# base_robot.net
KiCad netlist of a schematic drawn in EAGLE
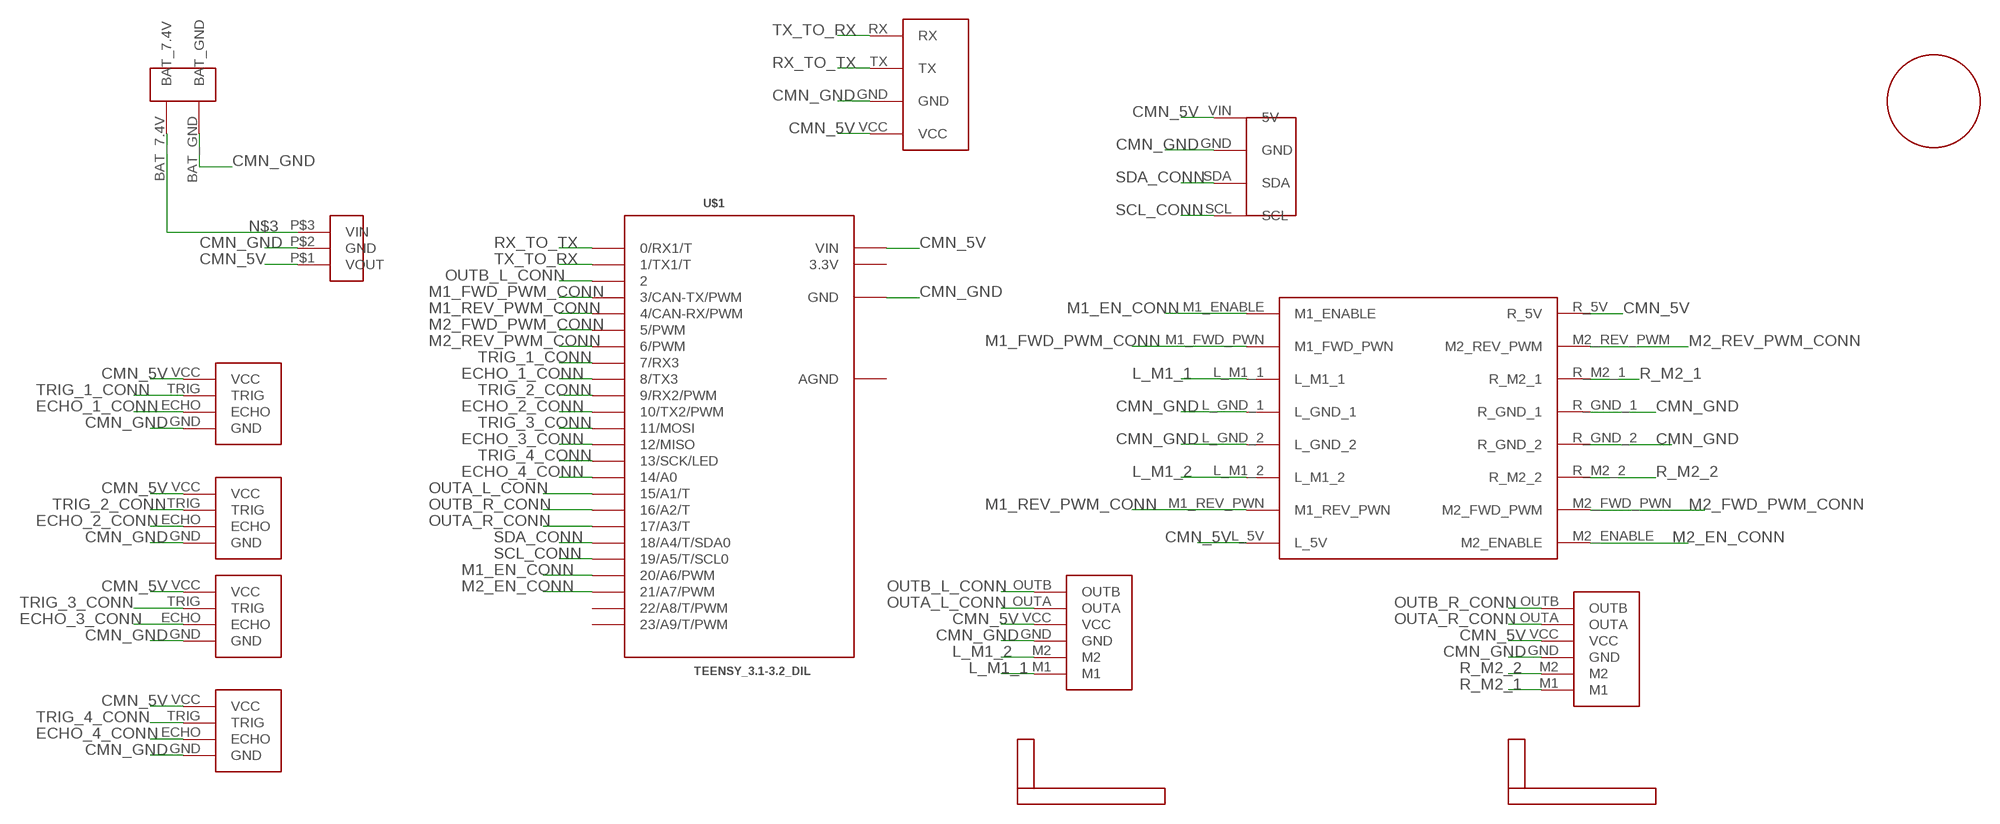
[diagram p0: schematic, sheet 1]

(export (version "E")
  (design (tool "Eeschema 10.0.6"))
  (components
    (comp (ref "U$1")
      (value "TEENSY_3.1-3.2_DIL")
      (footprint "eagle-import:TEENSY_3.0-3.2&LC_DIL")
      (libsource (lib "eagle-import") (part "TEENSY_3.1-3.2_DIL"))
    )
    (comp (ref "U$2")
      (value "MOTOR_DRIVER")
      (footprint "eagle-import:MOTOR_DRIVER")
      (libsource (lib "eagle-import") (part "MOTOR_DRIVER"))
    )
    (comp (ref "U$3")
      (value "VOLTAGE_REGULATOR")
      (footprint "eagle-import:VOLTAGE_REGULATOR")
      (libsource (lib "eagle-import") (part "VOLTAGE_REGULATOR"))
    )
    (comp (ref "U$4")
      (value "SONAR_SENSOR")
      (footprint "eagle-import:SONAR_SENSOR")
      (libsource (lib "eagle-import") (part "SONAR_SENSOR"))
    )
    (comp (ref "U$5")
      (value "SONAR_SENSOR")
      (footprint "eagle-import:SONAR_SENSOR")
      (libsource (lib "eagle-import") (part "SONAR_SENSOR"))
    )
    (comp (ref "U$6")
      (value "SONAR_SENSOR")
      (footprint "eagle-import:SONAR_SENSOR")
      (libsource (lib "eagle-import") (part "SONAR_SENSOR"))
    )
    (comp (ref "U$7")
      (value "SONAR_SENSOR")
      (footprint "eagle-import:SONAR_SENSOR")
      (libsource (lib "eagle-import") (part "SONAR_SENSOR"))
    )
    (comp (ref "U$8")
      (value "BATTERY_INPUT")
      (footprint "eagle-import:BATTERY_INPUT")
      (libsource (lib "eagle-import") (part "BATTERY_INPUT"))
    )
    (comp (ref "U$9")
      (value "MOTOR_ENCODER_25D")
      (footprint "eagle-import:MOTOR_ENCODER_25D")
      (libsource (lib "eagle-import") (part "MOTOR_ENCODER_25D"))
    )
    (comp (ref "U$10")
      (value "MOTOR_ENCODER_25D")
      (footprint "eagle-import:MOTOR_ENCODER_25D")
      (libsource (lib "eagle-import") (part "MOTOR_ENCODER_25D"))
    )
    (comp (ref "U$11")
      (value "IMU")
      (footprint "eagle-import:IMU")
      (libsource (lib "eagle-import") (part "IMU"))
    )
    (comp (ref "U$12")
      (value "HC05_BLUETOOTH")
      (footprint "eagle-import:HC05_BLUETOOTH")
      (libsource (lib "eagle-import") (part "HC05_BLUETOOTH"))
    )
    (comp (ref "U$13")
      (value "3_4_BALLCASTER")
      (footprint "eagle-import:3_4_BALLCASTER")
      (libsource (lib "eagle-import") (part "3_4_BALLCASTER"))
    )
    (comp (ref "U$14")
      (value "MOTOR_BRACKET_25D")
      (footprint "eagle-import:MOTOR_BRACKET_25D")
      (libsource (lib "eagle-import") (part "MOTOR_BRACKET_25D"))
    )
    (comp (ref "U$15")
      (value "MOTOR_BRACKET_25D")
      (footprint "eagle-import:MOTOR_BRACKET_25D")
      (libsource (lib "eagle-import") (part "MOTOR_BRACKET_25D"))
    )
  )
  (nets
    (net (code "1") (name "/3.3V") (class "Default")
      (node (ref "U$1") (pin "3.3V") (pinfunction "3.3V_3.3V") (pintype "power_in"))
    )
    (net (code "2") (name "/AGND") (class "Default")
      (node (ref "U$1") (pin "AGND") (pinfunction "AGND_AGND") (pintype "power_in"))
    )
    (net (code "3") (name "/CMN_5V") (class "Default")
      (node (ref "U$1") (pin "VIN") (pinfunction "VIN_VIN") (pintype "power_in"))
      (node (ref "U$10") (pin "VCC") (pinfunction "VCC_VCC") (pintype "bidirectional"))
      (node (ref "U$11") (pin "VIN") (pinfunction "5V_VIN") (pintype "bidirectional"))
      (node (ref "U$12") (pin "VCC") (pinfunction "VCC_VCC") (pintype "bidirectional"))
      (node (ref "U$2") (pin "L_5V") (pinfunction "L_5V_L_5V") (pintype "bidirectional"))
      (node (ref "U$2") (pin "R_5V") (pinfunction "R_5V_R_5V") (pintype "bidirectional"))
      (node (ref "U$3") (pin "P$1") (pinfunction "VOUT_P$1") (pintype "bidirectional"))
      (node (ref "U$4") (pin "VCC") (pinfunction "VCC_VCC") (pintype "bidirectional"))
      (node (ref "U$5") (pin "VCC") (pinfunction "VCC_VCC") (pintype "bidirectional"))
      (node (ref "U$6") (pin "VCC") (pinfunction "VCC_VCC") (pintype "bidirectional"))
      (node (ref "U$7") (pin "VCC") (pinfunction "VCC_VCC") (pintype "bidirectional"))
      (node (ref "U$9") (pin "VCC") (pinfunction "VCC_VCC") (pintype "bidirectional"))
    )
    (net (code "4") (name "/CMN_GND") (class "Default")
      (node (ref "U$1") (pin "GND") (pinfunction "GND_GND") (pintype "power_in"))
      (node (ref "U$10") (pin "GND") (pinfunction "GND_GND") (pintype "bidirectional"))
      (node (ref "U$11") (pin "GND") (pinfunction "GND_GND") (pintype "bidirectional"))
      (node (ref "U$12") (pin "GND") (pinfunction "GND_GND") (pintype "bidirectional"))
      (node (ref "U$2") (pin "L_GND_1") (pinfunction "L_GND_1_L_GND_1") (pintype "bidirectional"))
      (node (ref "U$2") (pin "L_GND_2") (pinfunction "L_GND_2_L_GND_2") (pintype "bidirectional"))
      (node (ref "U$2") (pin "R_GND_1") (pinfunction "R_GND_1_R_GND_1") (pintype "bidirectional"))
      (node (ref "U$2") (pin "R_GND_2") (pinfunction "R_GND_2_R_GND_2") (pintype "bidirectional"))
      (node (ref "U$3") (pin "P$2") (pinfunction "GND_P$2") (pintype "bidirectional"))
      (node (ref "U$4") (pin "GND") (pinfunction "GND_GND") (pintype "bidirectional"))
      (node (ref "U$5") (pin "GND") (pinfunction "GND_GND") (pintype "bidirectional"))
      (node (ref "U$6") (pin "GND") (pinfunction "GND_GND") (pintype "bidirectional"))
      (node (ref "U$7") (pin "GND") (pinfunction "GND_GND") (pintype "bidirectional"))
      (node (ref "U$8") (pin "BAT_GND") (pinfunction "BAT_GND_BAT_GND") (pintype "bidirectional"))
      (node (ref "U$9") (pin "GND") (pinfunction "GND_GND") (pintype "bidirectional"))
    )
    (net (code "5") (name "/ECHO_1_CONN") (class "Default")
      (node (ref "U$1") (pin "8") (pinfunction "8/TX3_8") (pintype "bidirectional"))
      (node (ref "U$4") (pin "ECHO") (pinfunction "ECHO_ECHO") (pintype "bidirectional"))
    )
    (net (code "6") (name "/ECHO_2_CONN") (class "Default")
      (node (ref "U$1") (pin "10") (pinfunction "10/TX2/PWM_10") (pintype "bidirectional"))
      (node (ref "U$5") (pin "ECHO") (pinfunction "ECHO_ECHO") (pintype "bidirectional"))
    )
    (net (code "7") (name "/ECHO_3_CONN") (class "Default")
      (node (ref "U$1") (pin "12") (pinfunction "12/MISO_12") (pintype "bidirectional"))
      (node (ref "U$6") (pin "ECHO") (pinfunction "ECHO_ECHO") (pintype "bidirectional"))
    )
    (net (code "8") (name "/ECHO_4_CONN") (class "Default")
      (node (ref "U$1") (pin "14/A0") (pinfunction "14/A0_14/A0") (pintype "bidirectional"))
      (node (ref "U$7") (pin "ECHO") (pinfunction "ECHO_ECHO") (pintype "bidirectional"))
    )
    (net (code "9") (name "/L_M1_1") (class "Default")
      (node (ref "U$2") (pin "L_M1_1") (pinfunction "L_M1_1_L_M1_1") (pintype "bidirectional"))
      (node (ref "U$9") (pin "M1") (pinfunction "M1_M1") (pintype "bidirectional"))
    )
    (net (code "10") (name "/L_M1_2") (class "Default")
      (node (ref "U$2") (pin "L_M1_2") (pinfunction "L_M1_2_L_M1_2") (pintype "bidirectional"))
      (node (ref "U$9") (pin "M2") (pinfunction "M2_M2") (pintype "bidirectional"))
    )
    (net (code "11") (name "/M1_EN_CONN") (class "Default")
      (node (ref "U$1") (pin "20/A6") (pinfunction "20/A6/PWM_20/A6") (pintype "bidirectional"))
      (node (ref "U$2") (pin "M1_ENABLE") (pinfunction "M1_ENABLE_M1_ENABLE") (pintype "bidirectional"))
    )
    (net (code "12") (name "/M1_FWD_PWM_CONN") (class "Default")
      (node (ref "U$1") (pin "3") (pinfunction "3/CAN-TX/PWM_3") (pintype "bidirectional"))
      (node (ref "U$2") (pin "M1_FWD_PWN") (pinfunction "M1_FWD_PWN_M1_FWD_PWN") (pintype "bidirectional"))
    )
    (net (code "13") (name "/M1_REV_PWM_CONN") (class "Default")
      (node (ref "U$1") (pin "4") (pinfunction "4/CAN-RX/PWM_4") (pintype "bidirectional"))
      (node (ref "U$2") (pin "M1_REV_PWN") (pinfunction "M1_REV_PWN_M1_REV_PWN") (pintype "bidirectional"))
    )
    (net (code "14") (name "/M2_EN_CONN") (class "Default")
      (node (ref "U$1") (pin "21/A7") (pinfunction "21/A7/PWM_21/A7") (pintype "bidirectional"))
      (node (ref "U$2") (pin "M2_ENABLE") (pinfunction "M2_ENABLE_M2_ENABLE") (pintype "bidirectional"))
    )
    (net (code "15") (name "/M2_FWD_PWM_CONN") (class "Default")
      (node (ref "U$1") (pin "5") (pinfunction "5/PWM_5") (pintype "bidirectional"))
      (node (ref "U$2") (pin "M2_FWD_PWN") (pinfunction "M2_FWD_PWM_M2_FWD_PWN") (pintype "bidirectional"))
    )
    (net (code "16") (name "/M2_REV_PWM_CONN") (class "Default")
      (node (ref "U$1") (pin "6") (pinfunction "6/PWM_6") (pintype "bidirectional"))
      (node (ref "U$2") (pin "M2_REV_PWM") (pinfunction "M2_REV_PWM_M2_REV_PWM") (pintype "bidirectional"))
    )
    (net (code "17") (name "/N$3") (class "Default")
      (node (ref "U$3") (pin "P$3") (pinfunction "VIN_P$3") (pintype "bidirectional"))
      (node (ref "U$8") (pin "BAT_7.4V") (pinfunction "BAT_7.4V_BAT_7.4V") (pintype "bidirectional"))
    )
    (net (code "18") (name "/OUTA_L_CONN") (class "Default")
      (node (ref "U$1") (pin "15/A1") (pinfunction "15/A1/T_15/A1") (pintype "bidirectional"))
      (node (ref "U$9") (pin "OUTA") (pinfunction "OUTA_OUTA") (pintype "bidirectional"))
    )
    (net (code "19") (name "/OUTA_R_CONN") (class "Default")
      (node (ref "U$1") (pin "17/A3") (pinfunction "17/A3/T_17/A3") (pintype "bidirectional"))
      (node (ref "U$10") (pin "OUTA") (pinfunction "OUTA_OUTA") (pintype "bidirectional"))
    )
    (net (code "20") (name "/OUTB_L_CONN") (class "Default")
      (node (ref "U$1") (pin "2") (pinfunction "2_2") (pintype "bidirectional"))
      (node (ref "U$9") (pin "OUTB") (pinfunction "OUTB_OUTB") (pintype "bidirectional"))
    )
    (net (code "21") (name "/OUTB_R_CONN") (class "Default")
      (node (ref "U$1") (pin "16/A2") (pinfunction "16/A2/T_16/A2") (pintype "bidirectional"))
      (node (ref "U$10") (pin "OUTB") (pinfunction "OUTB_OUTB") (pintype "bidirectional"))
    )
    (net (code "22") (name "/RX_TO_TX") (class "Default")
      (node (ref "U$1") (pin "0") (pinfunction "0/RX1/T_0") (pintype "bidirectional"))
      (node (ref "U$12") (pin "TX") (pinfunction "TX_TX") (pintype "bidirectional"))
    )
    (net (code "23") (name "/R_M2_1") (class "Default")
      (node (ref "U$10") (pin "M1") (pinfunction "M1_M1") (pintype "bidirectional"))
      (node (ref "U$2") (pin "R_M2_1") (pinfunction "R_M2_1_R_M2_1") (pintype "bidirectional"))
    )
    (net (code "24") (name "/R_M2_2") (class "Default")
      (node (ref "U$10") (pin "M2") (pinfunction "M2_M2") (pintype "bidirectional"))
      (node (ref "U$2") (pin "R_M2_2") (pinfunction "R_M2_2_R_M2_2") (pintype "bidirectional"))
    )
    (net (code "25") (name "/SCL_CONN") (class "Default")
      (node (ref "U$1") (pin "19/A5") (pinfunction "19/A5/T/SCL0_19/A5") (pintype "bidirectional"))
      (node (ref "U$11") (pin "SCL") (pinfunction "SCL_SCL") (pintype "bidirectional"))
    )
    (net (code "26") (name "/SDA_CONN") (class "Default")
      (node (ref "U$1") (pin "18/A4") (pinfunction "18/A4/T/SDA0_18/A4") (pintype "bidirectional"))
      (node (ref "U$11") (pin "SDA") (pinfunction "SDA_SDA") (pintype "bidirectional"))
    )
    (net (code "27") (name "/TRIG_1_CONN") (class "Default")
      (node (ref "U$1") (pin "7") (pinfunction "7/RX3_7") (pintype "bidirectional"))
      (node (ref "U$4") (pin "TRIG") (pinfunction "TRIG_TRIG") (pintype "bidirectional"))
    )
    (net (code "28") (name "/TRIG_2_CONN") (class "Default")
      (node (ref "U$1") (pin "9") (pinfunction "9/RX2/PWM_9") (pintype "bidirectional"))
      (node (ref "U$5") (pin "TRIG") (pinfunction "TRIG_TRIG") (pintype "bidirectional"))
    )
    (net (code "29") (name "/TRIG_3_CONN") (class "Default")
      (node (ref "U$1") (pin "11") (pinfunction "11/MOSI_11") (pintype "bidirectional"))
      (node (ref "U$6") (pin "TRIG") (pinfunction "TRIG_TRIG") (pintype "bidirectional"))
    )
    (net (code "30") (name "/TRIG_4_CONN") (class "Default")
      (node (ref "U$1") (pin "13") (pinfunction "13/SCK/LED_13") (pintype "bidirectional"))
      (node (ref "U$7") (pin "TRIG") (pinfunction "TRIG_TRIG") (pintype "bidirectional"))
    )
    (net (code "31") (name "/TX_TO_RX") (class "Default")
      (node (ref "U$1") (pin "1") (pinfunction "1/TX1/T_1") (pintype "bidirectional"))
      (node (ref "U$12") (pin "RX") (pinfunction "RX_RX") (pintype "bidirectional"))
    )
    (net (code "32") (name "unconnected-(U$1-22{slash}A8{slash}T{slash}PWM-Pad22{slash}A8)") (class "Default")
      (node (ref "U$1") (pin "22/A8") (pinfunction "22/A8/T/PWM_22/A8") (pintype "bidirectional"))
    )
    (net (code "33") (name "unconnected-(U$1-23{slash}A9{slash}T{slash}PWM-Pad23{slash}A9)") (class "Default")
      (node (ref "U$1") (pin "23/A9") (pinfunction "23/A9/T/PWM_23/A9") (pintype "bidirectional"))
    )
  )
)
